# FPGA_BANKS.net
KiCad netlist of a schematic drawn in Altium Designer
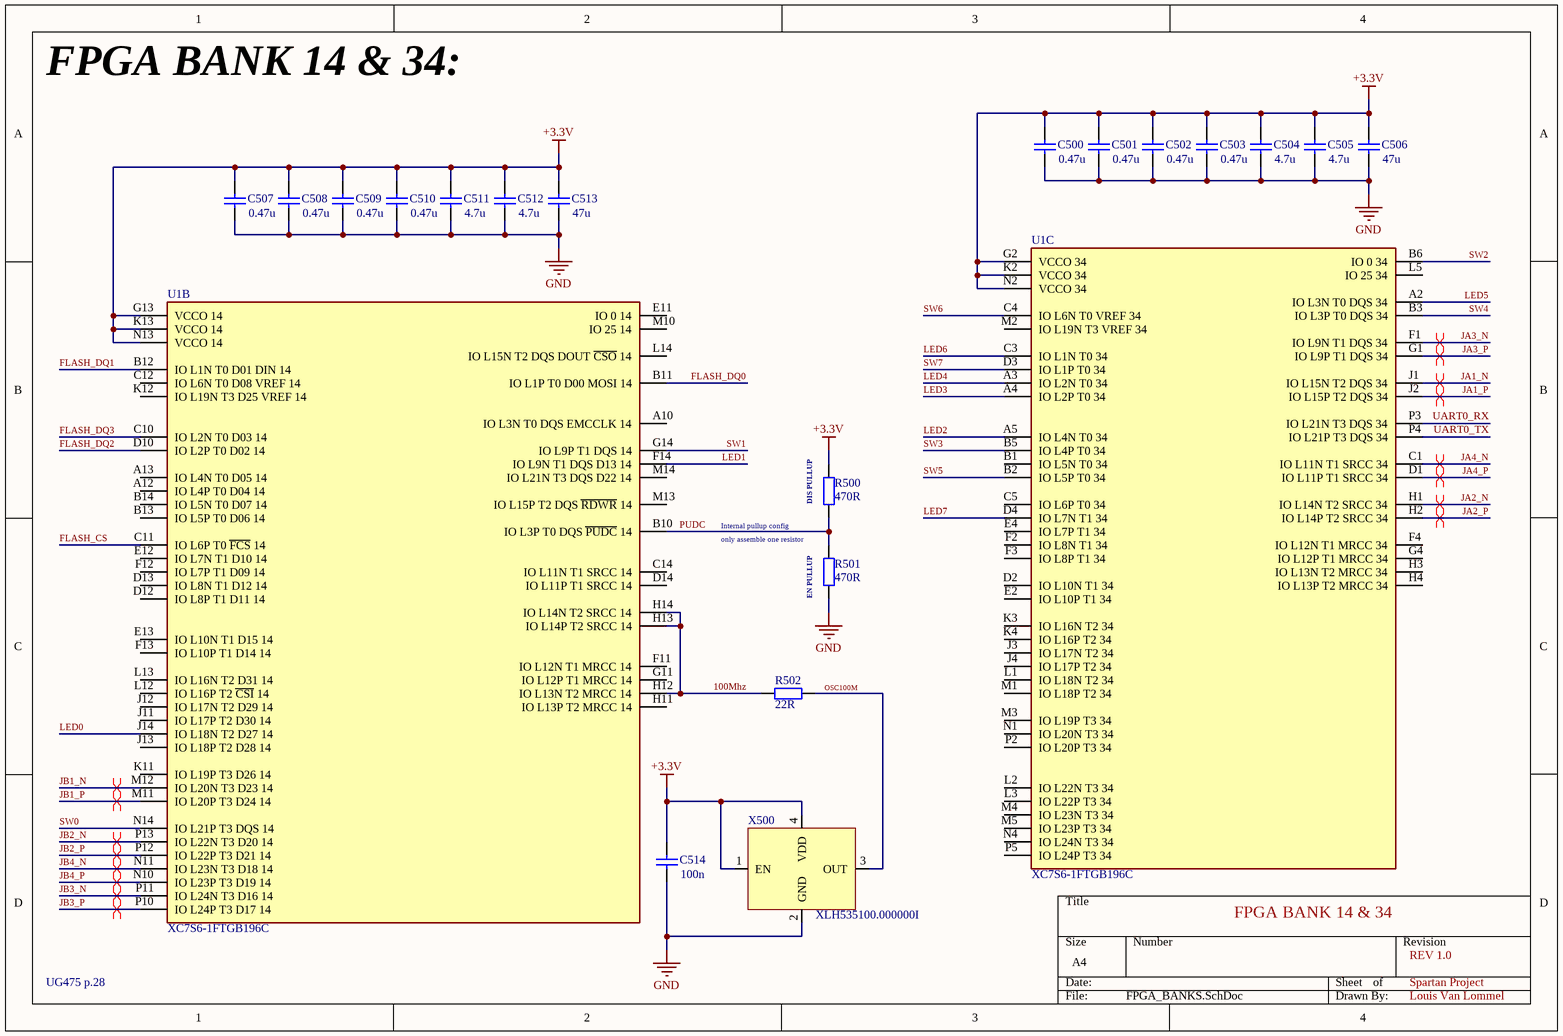
[diagram p0: FPGA_BANKS.SchDoc]

(export (version "E")
  (design (tool "Eeschema 10.0.6"))
  (components
    (comp (ref "C500")
      (value "0.47u")
      (footprint "CAP_0402")
      (description "Capacitor")
      (fields (field (name "Comment") "0.47uF") (field (name "PUBLISHER") "Altium Limited"))
      (libsource (lib "Miscellaneous Devices") (part "Cap"))
    )
    (comp (ref "C501")
      (value "0.47u")
      (footprint "CAP_0402")
      (description "Capacitor")
      (fields (field (name "Comment") "0.47uF") (field (name "PUBLISHER") "Altium Limited"))
      (libsource (lib "Miscellaneous Devices") (part "Cap"))
    )
    (comp (ref "C502")
      (value "0.47u")
      (footprint "CAP_0402")
      (description "Capacitor")
      (fields (field (name "Comment") "0.47uF") (field (name "PUBLISHER") "Altium Limited"))
      (libsource (lib "Miscellaneous Devices") (part "Cap"))
    )
    (comp (ref "C503")
      (value "0.47u")
      (footprint "CAP_0402")
      (description "Capacitor")
      (fields (field (name "Comment") "0.47uF") (field (name "PUBLISHER") "Altium Limited"))
      (libsource (lib "Miscellaneous Devices") (part "Cap"))
    )
    (comp (ref "C504")
      (value "4.7u")
      (footprint "CAP_0402")
      (description "Capacitor")
      (fields (field (name "PUBLISHER") "Altium Limited"))
      (libsource (lib "Miscellaneous Devices") (part "Cap"))
    )
    (comp (ref "C505")
      (value "4.7u")
      (footprint "CAP_0402")
      (description "Capacitor")
      (fields (field (name "PUBLISHER") "Altium Limited"))
      (libsource (lib "Miscellaneous Devices") (part "Cap"))
    )
    (comp (ref "C506")
      (value "47u")
      (footprint "CAP_0603")
      (description "Capacitor")
      (fields (field (name "Comment") "47uF") (field (name "PUBLISHER") "Altium Limited"))
      (libsource (lib "Miscellaneous Devices") (part "Cap"))
    )
    (comp (ref "C507")
      (value "0.47u")
      (footprint "CAP_0402")
      (description "Capacitor")
      (fields (field (name "Comment") "0.47uF") (field (name "PUBLISHER") "Altium Limited"))
      (libsource (lib "Miscellaneous Devices") (part "Cap"))
    )
    (comp (ref "C508")
      (value "0.47u")
      (footprint "CAP_0402")
      (description "Capacitor")
      (fields (field (name "Comment") "0.47uF") (field (name "PUBLISHER") "Altium Limited"))
      (libsource (lib "Miscellaneous Devices") (part "Cap"))
    )
    (comp (ref "C509")
      (value "0.47u")
      (footprint "CAP_0402")
      (description "Capacitor")
      (fields (field (name "Comment") "0.47uF") (field (name "PUBLISHER") "Altium Limited"))
      (libsource (lib "Miscellaneous Devices") (part "Cap"))
    )
    (comp (ref "C510")
      (value "0.47u")
      (footprint "CAP_0402")
      (description "Capacitor")
      (fields (field (name "Comment") "0.47uF") (field (name "PUBLISHER") "Altium Limited"))
      (libsource (lib "Miscellaneous Devices") (part "Cap"))
    )
    (comp (ref "C511")
      (value "4.7u")
      (footprint "CAP_0402")
      (description "Capacitor")
      (fields (field (name "PUBLISHER") "Altium Limited"))
      (libsource (lib "Miscellaneous Devices") (part "Cap"))
    )
    (comp (ref "C512")
      (value "4.7u")
      (footprint "CAP_0402")
      (description "Capacitor")
      (fields (field (name "PUBLISHER") "Altium Limited"))
      (libsource (lib "Miscellaneous Devices") (part "Cap"))
    )
    (comp (ref "C513")
      (value "47u")
      (footprint "CAP_0603")
      (description "Capacitor")
      (fields (field (name "Comment") "47uF") (field (name "PUBLISHER") "Altium Limited"))
      (libsource (lib "Miscellaneous Devices") (part "Cap"))
    )
    (comp (ref "C514")
      (value "100n")
      (footprint "CAP_0603")
      (description "Capacitor")
      (fields (field (name "PUBLISHER") "Altium Limited"))
      (libsource (lib "Miscellaneous Devices") (part "Cap"))
    )
    (comp (ref "R500")
      (value "470R")
      (footprint "RES_0603")
      (description "Resistor")
      (fields (field (name "Comment") "470") (field (name "PUBLISHER") "Altium Limited"))
      (libsource (lib "Miscellaneous Devices") (part "Res2"))
    )
    (comp (ref "R501")
      (value "470R")
      (footprint "RES_0603")
      (description "Resistor Enable pullup BANK FPGA")
      (fields (field (name "Comment") "470 DNP") (field (name "PUBLISHER") "Altium Limited"))
      (libsource (lib "Miscellaneous Devices") (part "Res2"))
    )
    (comp (ref "R502")
      (value "22R")
      (footprint "RES_0603")
      (description "Resistor")
      (fields (field (name "Comment") "22") (field (name "PUBLISHER") "Altium Limited"))
      (libsource (lib "") (part "Res2_1"))
    )
    (comp (ref "U1")
      (value "XC7S6-1FTGB196C")
      (footprint "FP-XC7S6-1FTGB196C-MFG")
      (fields
        (field (name "MANUFACTURER") "Xilinx")
        (field (name "OCTOPART") "https://octopart.com/xc7s6-1ftgb196c-xilinx-81890684")
      )
      (libsource (lib "Altium Content Vault") (part "4382e9425a5ef0cb43184b1739abe55"))
    )
    (comp (ref "X500")
      (value "XLH535100.000000I")
      (footprint "5X3.2MM CRYSTAL")
      (description "12Mhz oscillator")
      (libsource (lib "Schematic_Symbols") (part "Oscillator"))
    )
  )
  (nets
    (net (code "1") (name "+3.3V") (class "Default")
      (node (ref "C500") (pin "2") (pinfunction "2_2") (pintype "passive"))
      (node (ref "C501") (pin "2") (pinfunction "2_2") (pintype "passive"))
      (node (ref "C502") (pin "2") (pinfunction "2_2") (pintype "passive"))
      (node (ref "C503") (pin "2") (pinfunction "2_2") (pintype "passive"))
      (node (ref "C504") (pin "2") (pinfunction "2_2") (pintype "passive"))
      (node (ref "C505") (pin "2") (pinfunction "2_2") (pintype "passive"))
      (node (ref "C506") (pin "2") (pinfunction "2_2") (pintype "passive"))
      (node (ref "C507") (pin "2") (pinfunction "2_2") (pintype "passive"))
      (node (ref "C508") (pin "2") (pinfunction "2_2") (pintype "passive"))
      (node (ref "C509") (pin "2") (pinfunction "2_2") (pintype "passive"))
      (node (ref "C510") (pin "2") (pinfunction "2_2") (pintype "passive"))
      (node (ref "C511") (pin "2") (pinfunction "2_2") (pintype "passive"))
      (node (ref "C512") (pin "2") (pinfunction "2_2") (pintype "passive"))
      (node (ref "C513") (pin "2") (pinfunction "2_2") (pintype "passive"))
      (node (ref "C514") (pin "2") (pinfunction "2_2") (pintype "passive"))
      (node (ref "R500") (pin "2") (pinfunction "2_2") (pintype "passive"))
      (node (ref "U1") (pin "G13") (pinfunction "VCCO_14_G13") (pintype "passive"))
      (node (ref "U1") (pin "G2") (pinfunction "VCCO_34_G2") (pintype "passive"))
      (node (ref "U1") (pin "K13") (pinfunction "VCCO_14_K13") (pintype "passive"))
      (node (ref "U1") (pin "K2") (pinfunction "VCCO_34_K2") (pintype "passive"))
      (node (ref "U1") (pin "N13") (pinfunction "VCCO_14_N13") (pintype "passive"))
      (node (ref "U1") (pin "N2") (pinfunction "VCCO_34_N2") (pintype "passive"))
      (node (ref "X500") (pin "1") (pinfunction "EN_1") (pintype "passive"))
      (node (ref "X500") (pin "4") (pinfunction "VDD_4") (pintype "passive"))
    )
    (net (code "2") (name "/100Mhz") (class "Default")
      (node (ref "R502") (pin "2") (pinfunction "2_2") (pintype "passive"))
      (node (ref "U1") (pin "H12") (pinfunction "IO_L13N_T2_MRCC_14_H12") (pintype "passive"))
      (node (ref "U1") (pin "H13") (pinfunction "IO_L14P_T2_SRCC_14_H13") (pintype "passive"))
      (node (ref "U1") (pin "H14") (pinfunction "IO_L14N_T2_SRCC_14_H14") (pintype "passive"))
    )
    (net (code "3") (name "/FLASH_CS") (class "Default")
      (node (ref "U1") (pin "C11") (pinfunction "IO_L6P_T0_~{FCS}_14_C11") (pintype "passive"))
    )
    (net (code "4") (name "/FLASH_DQ0") (class "Default")
      (node (ref "U1") (pin "B11") (pinfunction "IO_L1P_T0_D00_MOSI_14_B11") (pintype "passive"))
    )
    (net (code "5") (name "/FLASH_DQ1") (class "Default")
      (node (ref "U1") (pin "B12") (pinfunction "IO_L1N_T0_D01_DIN_14_B12") (pintype "passive"))
    )
    (net (code "6") (name "/FLASH_DQ2") (class "Default")
      (node (ref "U1") (pin "D10") (pinfunction "IO_L2P_T0_D02_14_D10") (pintype "passive"))
    )
    (net (code "7") (name "/FLASH_DQ3") (class "Default")
      (node (ref "U1") (pin "C10") (pinfunction "IO_L2N_T0_D03_14_C10") (pintype "passive"))
    )
    (net (code "8") (name "/JA1_N") (class "Default")
      (node (ref "U1") (pin "J1") (pinfunction "IO_L15N_T2_DQS_34_J1") (pintype "passive"))
    )
    (net (code "9") (name "/JA1_P") (class "Default")
      (node (ref "U1") (pin "J2") (pinfunction "IO_L15P_T2_DQS_34_J2") (pintype "passive"))
    )
    (net (code "10") (name "/JA2_N") (class "Default")
      (node (ref "U1") (pin "H1") (pinfunction "IO_L14N_T2_SRCC_34_H1") (pintype "passive"))
    )
    (net (code "11") (name "/JA2_P") (class "Default")
      (node (ref "U1") (pin "H2") (pinfunction "IO_L14P_T2_SRCC_34_H2") (pintype "passive"))
    )
    (net (code "12") (name "/JA3_N") (class "Default")
      (node (ref "U1") (pin "F1") (pinfunction "IO_L9N_T1_DQS_34_F1") (pintype "passive"))
    )
    (net (code "13") (name "/JA3_P") (class "Default")
      (node (ref "U1") (pin "G1") (pinfunction "IO_L9P_T1_DQS_34_G1") (pintype "passive"))
    )
    (net (code "14") (name "/JA4_N") (class "Default")
      (node (ref "U1") (pin "C1") (pinfunction "IO_L11N_T1_SRCC_34_C1") (pintype "passive"))
    )
    (net (code "15") (name "/JA4_P") (class "Default")
      (node (ref "U1") (pin "D1") (pinfunction "IO_L11P_T1_SRCC_34_D1") (pintype "passive"))
    )
    (net (code "16") (name "/JB1_N") (class "Default")
      (node (ref "U1") (pin "M12") (pinfunction "IO_L20N_T3_D23_14_M12") (pintype "passive"))
    )
    (net (code "17") (name "/JB1_P") (class "Default")
      (node (ref "U1") (pin "M11") (pinfunction "IO_L20P_T3_D24_14_M11") (pintype "passive"))
    )
    (net (code "18") (name "/JB2_N") (class "Default")
      (node (ref "U1") (pin "P13") (pinfunction "IO_L22N_T3_D20_14_P13") (pintype "passive"))
    )
    (net (code "19") (name "/JB2_P") (class "Default")
      (node (ref "U1") (pin "P12") (pinfunction "IO_L22P_T3_D21_14_P12") (pintype "passive"))
    )
    (net (code "20") (name "/JB3_N") (class "Default")
      (node (ref "U1") (pin "P11") (pinfunction "IO_L24N_T3_D16_14_P11") (pintype "passive"))
    )
    (net (code "21") (name "/JB3_P") (class "Default")
      (node (ref "U1") (pin "P10") (pinfunction "IO_L24P_T3_D17_14_P10") (pintype "passive"))
    )
    (net (code "22") (name "/JB4_N") (class "Default")
      (node (ref "U1") (pin "N11") (pinfunction "IO_L23N_T3_D18_14_N11") (pintype "passive"))
    )
    (net (code "23") (name "/JB4_P") (class "Default")
      (node (ref "U1") (pin "N10") (pinfunction "IO_L23P_T3_D19_14_N10") (pintype "passive"))
    )
    (net (code "24") (name "/LED0") (class "Default")
      (node (ref "U1") (pin "J14") (pinfunction "IO_L18N_T2_D27_14_J14") (pintype "passive"))
    )
    (net (code "25") (name "/LED1") (class "Default")
      (node (ref "U1") (pin "F14") (pinfunction "IO_L9N_T1_DQS_D13_14_F14") (pintype "passive"))
    )
    (net (code "26") (name "/LED2") (class "Default")
      (node (ref "U1") (pin "A5") (pinfunction "IO_L4N_T0_34_A5") (pintype "passive"))
    )
    (net (code "27") (name "/LED3") (class "Default")
      (node (ref "U1") (pin "A4") (pinfunction "IO_L2P_T0_34_A4") (pintype "passive"))
    )
    (net (code "28") (name "/LED4") (class "Default")
      (node (ref "U1") (pin "A3") (pinfunction "IO_L2N_T0_34_A3") (pintype "passive"))
    )
    (net (code "29") (name "/LED5") (class "Default")
      (node (ref "U1") (pin "A2") (pinfunction "IO_L3N_T0_DQS_34_A2") (pintype "passive"))
    )
    (net (code "30") (name "/LED6") (class "Default")
      (node (ref "U1") (pin "C3") (pinfunction "IO_L1N_T0_34_C3") (pintype "passive"))
    )
    (net (code "31") (name "/LED7") (class "Default")
      (node (ref "U1") (pin "D4") (pinfunction "IO_L7N_T1_34_D4") (pintype "passive"))
    )
    (net (code "32") (name "/OSC100M") (class "Default")
      (node (ref "R502") (pin "1") (pinfunction "1_1") (pintype "passive"))
      (node (ref "X500") (pin "3") (pinfunction "OUT_3") (pintype "passive"))
    )
    (net (code "33") (name "/PUDC") (class "Default")
      (node (ref "R500") (pin "1") (pinfunction "1_1") (pintype "passive"))
      (node (ref "R501") (pin "2") (pinfunction "2_2") (pintype "passive"))
      (node (ref "U1") (pin "B10") (pinfunction "IO_L3P_T0_DQS_~{PUDC}_14_B10") (pintype "passive"))
    )
    (net (code "34") (name "/SW0") (class "Default")
      (node (ref "U1") (pin "N14") (pinfunction "IO_L21P_T3_DQS_14_N14") (pintype "passive"))
    )
    (net (code "35") (name "/SW1") (class "Default")
      (node (ref "U1") (pin "G14") (pinfunction "IO_L9P_T1_DQS_14_G14") (pintype "passive"))
    )
    (net (code "36") (name "/SW2") (class "Default")
      (node (ref "U1") (pin "B6") (pinfunction "IO_0_34_B6") (pintype "passive"))
    )
    (net (code "37") (name "/SW3") (class "Default")
      (node (ref "U1") (pin "B5") (pinfunction "IO_L4P_T0_34_B5") (pintype "passive"))
    )
    (net (code "38") (name "/SW4") (class "Default")
      (node (ref "U1") (pin "B3") (pinfunction "IO_L3P_T0_DQS_34_B3") (pintype "passive"))
    )
    (net (code "39") (name "/SW5") (class "Default")
      (node (ref "U1") (pin "B2") (pinfunction "IO_L5P_T0_34_B2") (pintype "passive"))
    )
    (net (code "40") (name "/SW6") (class "Default")
      (node (ref "U1") (pin "C4") (pinfunction "IO_L6N_T0_VREF_34_C4") (pintype "passive"))
    )
    (net (code "41") (name "/SW7") (class "Default")
      (node (ref "U1") (pin "D3") (pinfunction "IO_L1P_T0_34_D3") (pintype "passive"))
    )
    (net (code "42") (name "/UART0_RX") (class "Default")
      (node (ref "U1") (pin "P3") (pinfunction "IO_L21N_T3_DQS_34_P3") (pintype "passive"))
    )
    (net (code "43") (name "/UART0_TX") (class "Default")
      (node (ref "U1") (pin "P4") (pinfunction "IO_L21P_T3_DQS_34_P4") (pintype "passive"))
    )
    (net (code "44") (name "GND") (class "Default")
      (node (ref "C500") (pin "1") (pinfunction "1_1") (pintype "passive"))
      (node (ref "C501") (pin "1") (pinfunction "1_1") (pintype "passive"))
      (node (ref "C502") (pin "1") (pinfunction "1_1") (pintype "passive"))
      (node (ref "C503") (pin "1") (pinfunction "1_1") (pintype "passive"))
      (node (ref "C504") (pin "1") (pinfunction "1_1") (pintype "passive"))
      (node (ref "C505") (pin "1") (pinfunction "1_1") (pintype "passive"))
      (node (ref "C506") (pin "1") (pinfunction "1_1") (pintype "passive"))
      (node (ref "C507") (pin "1") (pinfunction "1_1") (pintype "passive"))
      (node (ref "C508") (pin "1") (pinfunction "1_1") (pintype "passive"))
      (node (ref "C509") (pin "1") (pinfunction "1_1") (pintype "passive"))
      (node (ref "C510") (pin "1") (pinfunction "1_1") (pintype "passive"))
      (node (ref "C511") (pin "1") (pinfunction "1_1") (pintype "passive"))
      (node (ref "C512") (pin "1") (pinfunction "1_1") (pintype "passive"))
      (node (ref "C513") (pin "1") (pinfunction "1_1") (pintype "passive"))
      (node (ref "C514") (pin "1") (pinfunction "1_1") (pintype "passive"))
      (node (ref "R501") (pin "1") (pinfunction "1_1") (pintype "passive"))
      (node (ref "X500") (pin "2") (pinfunction "GND_2") (pintype "passive"))
    )
    (net (code "45") (name "unconnected-(U1B-IO_0_14-PadE11)") (class "Default")
      (node (ref "U1") (pin "E11") (pinfunction "IO_0_14_E11") (pintype "passive"))
    )
    (net (code "46") (name "unconnected-(U1B-IO_25_14-PadM10)") (class "Default")
      (node (ref "U1") (pin "M10") (pinfunction "IO_25_14_M10") (pintype "passive"))
    )
    (net (code "47") (name "unconnected-(U1B-IO_L3N_T0_DQS_EMCCLK_14-PadA10)") (class "Default")
      (node (ref "U1") (pin "A10") (pinfunction "IO_L3N_T0_DQS_EMCCLK_14_A10") (pintype "passive"))
    )
    (net (code "48") (name "unconnected-(U1B-IO_L4N_T0_D05_14-PadA13)") (class "Default")
      (node (ref "U1") (pin "A13") (pinfunction "IO_L4N_T0_D05_14_A13") (pintype "passive"))
    )
    (net (code "49") (name "unconnected-(U1B-IO_L4P_T0_D04_14-PadA12)") (class "Default")
      (node (ref "U1") (pin "A12") (pinfunction "IO_L4P_T0_D04_14_A12") (pintype "passive"))
    )
    (net (code "50") (name "unconnected-(U1B-IO_L5N_T0_D07_14-PadB14)") (class "Default")
      (node (ref "U1") (pin "B14") (pinfunction "IO_L5N_T0_D07_14_B14") (pintype "passive"))
    )
    (net (code "51") (name "unconnected-(U1B-IO_L5P_T0_D06_14-PadB13)") (class "Default")
      (node (ref "U1") (pin "B13") (pinfunction "IO_L5P_T0_D06_14_B13") (pintype "passive"))
    )
    (net (code "52") (name "unconnected-(U1B-IO_L6N_T0_D08_VREF_14-PadC12)") (class "Default")
      (node (ref "U1") (pin "C12") (pinfunction "IO_L6N_T0_D08_VREF_14_C12") (pintype "passive"))
    )
    (net (code "53") (name "unconnected-(U1B-IO_L7N_T1_D10_14-PadE12)") (class "Default")
      (node (ref "U1") (pin "E12") (pinfunction "IO_L7N_T1_D10_14_E12") (pintype "passive"))
    )
    (net (code "54") (name "unconnected-(U1B-IO_L7P_T1_D09_14-PadF12)") (class "Default")
      (node (ref "U1") (pin "F12") (pinfunction "IO_L7P_T1_D09_14_F12") (pintype "passive"))
    )
    (net (code "55") (name "unconnected-(U1B-IO_L8N_T1_D12_14-PadD13)") (class "Default")
      (node (ref "U1") (pin "D13") (pinfunction "IO_L8N_T1_D12_14_D13") (pintype "passive"))
    )
    (net (code "56") (name "unconnected-(U1B-IO_L8P_T1_D11_14-PadD12)") (class "Default")
      (node (ref "U1") (pin "D12") (pinfunction "IO_L8P_T1_D11_14_D12") (pintype "passive"))
    )
    (net (code "57") (name "unconnected-(U1B-IO_L10N_T1_D15_14-PadE13)") (class "Default")
      (node (ref "U1") (pin "E13") (pinfunction "IO_L10N_T1_D15_14_E13") (pintype "passive"))
    )
    (net (code "58") (name "unconnected-(U1B-IO_L10P_T1_D14_14-PadF13)") (class "Default")
      (node (ref "U1") (pin "F13") (pinfunction "IO_L10P_T1_D14_14_F13") (pintype "passive"))
    )
    (net (code "59") (name "unconnected-(U1B-IO_L11N_T1_SRCC_14-PadC14)") (class "Default")
      (node (ref "U1") (pin "C14") (pinfunction "IO_L11N_T1_SRCC_14_C14") (pintype "passive"))
    )
    (net (code "60") (name "unconnected-(U1B-IO_L11P_T1_SRCC_14-PadD14)") (class "Default")
      (node (ref "U1") (pin "D14") (pinfunction "IO_L11P_T1_SRCC_14_D14") (pintype "passive"))
    )
    (net (code "61") (name "unconnected-(U1B-IO_L12N_T1_MRCC_14-PadF11)") (class "Default")
      (node (ref "U1") (pin "F11") (pinfunction "IO_L12N_T1_MRCC_14_F11") (pintype "passive"))
    )
    (net (code "62") (name "unconnected-(U1B-IO_L12P_T1_MRCC_14-PadG11)") (class "Default")
      (node (ref "U1") (pin "G11") (pinfunction "IO_L12P_T1_MRCC_14_G11") (pintype "passive"))
    )
    (net (code "63") (name "unconnected-(U1B-IO_L13P_T2_MRCC_14-PadH11)") (class "Default")
      (node (ref "U1") (pin "H11") (pinfunction "IO_L13P_T2_MRCC_14_H11") (pintype "passive"))
    )
    (net (code "64") (name "unconnected-(U1B-IO_L15N_T2_DQS_DOUT_~{CSO}_14-PadL14)") (class "Default")
      (node (ref "U1") (pin "L14") (pinfunction "IO_L15N_T2_DQS_DOUT_~{CSO}_14_L14") (pintype "passive"))
    )
    (net (code "65") (name "unconnected-(U1B-IO_L15P_T2_DQS_~{RDWR}_14-PadM13)") (class "Default")
      (node (ref "U1") (pin "M13") (pinfunction "IO_L15P_T2_DQS_~{RDWR}_14_M13") (pintype "passive"))
    )
    (net (code "66") (name "unconnected-(U1B-IO_L16N_T2_D31_14-PadL13)") (class "Default")
      (node (ref "U1") (pin "L13") (pinfunction "IO_L16N_T2_D31_14_L13") (pintype "passive"))
    )
    (net (code "67") (name "unconnected-(U1B-IO_L16P_T2_~{CSI}_14-PadL12)") (class "Default")
      (node (ref "U1") (pin "L12") (pinfunction "IO_L16P_T2_~{CSI}_14_L12") (pintype "passive"))
    )
    (net (code "68") (name "unconnected-(U1B-IO_L17N_T2_D29_14-PadJ12)") (class "Default")
      (node (ref "U1") (pin "J12") (pinfunction "IO_L17N_T2_D29_14_J12") (pintype "passive"))
    )
    (net (code "69") (name "unconnected-(U1B-IO_L17P_T2_D30_14-PadJ11)") (class "Default")
      (node (ref "U1") (pin "J11") (pinfunction "IO_L17P_T2_D30_14_J11") (pintype "passive"))
    )
    (net (code "70") (name "unconnected-(U1B-IO_L18P_T2_D28_14-PadJ13)") (class "Default")
      (node (ref "U1") (pin "J13") (pinfunction "IO_L18P_T2_D28_14_J13") (pintype "passive"))
    )
    (net (code "71") (name "unconnected-(U1B-IO_L19N_T3_D25_VREF_14-PadK12)") (class "Default")
      (node (ref "U1") (pin "K12") (pinfunction "IO_L19N_T3_D25_VREF_14_K12") (pintype "passive"))
    )
    (net (code "72") (name "unconnected-(U1B-IO_L19P_T3_D26_14-PadK11)") (class "Default")
      (node (ref "U1") (pin "K11") (pinfunction "IO_L19P_T3_D26_14_K11") (pintype "passive"))
    )
    (net (code "73") (name "unconnected-(U1B-IO_L21N_T3_DQS_D22_14-PadM14)") (class "Default")
      (node (ref "U1") (pin "M14") (pinfunction "IO_L21N_T3_DQS_D22_14_M14") (pintype "passive"))
    )
    (net (code "74") (name "unconnected-(U1C-IO_25_34-PadL5)") (class "Default")
      (node (ref "U1") (pin "L5") (pinfunction "IO_25_34_L5") (pintype "passive"))
    )
    (net (code "75") (name "unconnected-(U1C-IO_L5N_T0_34-PadB1)") (class "Default")
      (node (ref "U1") (pin "B1") (pinfunction "IO_L5N_T0_34_B1") (pintype "passive"))
    )
    (net (code "76") (name "unconnected-(U1C-IO_L6P_T0_34-PadC5)") (class "Default")
      (node (ref "U1") (pin "C5") (pinfunction "IO_L6P_T0_34_C5") (pintype "passive"))
    )
    (net (code "77") (name "unconnected-(U1C-IO_L7P_T1_34-PadE4)") (class "Default")
      (node (ref "U1") (pin "E4") (pinfunction "IO_L7P_T1_34_E4") (pintype "passive"))
    )
    (net (code "78") (name "unconnected-(U1C-IO_L8N_T1_34-PadF2)") (class "Default")
      (node (ref "U1") (pin "F2") (pinfunction "IO_L8N_T1_34_F2") (pintype "passive"))
    )
    (net (code "79") (name "unconnected-(U1C-IO_L8P_T1_34-PadF3)") (class "Default")
      (node (ref "U1") (pin "F3") (pinfunction "IO_L8P_T1_34_F3") (pintype "passive"))
    )
    (net (code "80") (name "unconnected-(U1C-IO_L10N_T1_34-PadD2)") (class "Default")
      (node (ref "U1") (pin "D2") (pinfunction "IO_L10N_T1_34_D2") (pintype "passive"))
    )
    (net (code "81") (name "unconnected-(U1C-IO_L10P_T1_34-PadE2)") (class "Default")
      (node (ref "U1") (pin "E2") (pinfunction "IO_L10P_T1_34_E2") (pintype "passive"))
    )
    (net (code "82") (name "unconnected-(U1C-IO_L12N_T1_MRCC_34-PadF4)") (class "Default")
      (node (ref "U1") (pin "F4") (pinfunction "IO_L12N_T1_MRCC_34_F4") (pintype "passive"))
    )
    (net (code "83") (name "unconnected-(U1C-IO_L12P_T1_MRCC_34-PadG4)") (class "Default")
      (node (ref "U1") (pin "G4") (pinfunction "IO_L12P_T1_MRCC_34_G4") (pintype "passive"))
    )
    (net (code "84") (name "unconnected-(U1C-IO_L13N_T2_MRCC_34-PadH3)") (class "Default")
      (node (ref "U1") (pin "H3") (pinfunction "IO_L13N_T2_MRCC_34_H3") (pintype "passive"))
    )
    (net (code "85") (name "unconnected-(U1C-IO_L13P_T2_MRCC_34-PadH4)") (class "Default")
      (node (ref "U1") (pin "H4") (pinfunction "IO_L13P_T2_MRCC_34_H4") (pintype "passive"))
    )
    (net (code "86") (name "unconnected-(U1C-IO_L16N_T2_34-PadK3)") (class "Default")
      (node (ref "U1") (pin "K3") (pinfunction "IO_L16N_T2_34_K3") (pintype "passive"))
    )
    (net (code "87") (name "unconnected-(U1C-IO_L16P_T2_34-PadK4)") (class "Default")
      (node (ref "U1") (pin "K4") (pinfunction "IO_L16P_T2_34_K4") (pintype "passive"))
    )
    (net (code "88") (name "unconnected-(U1C-IO_L17N_T2_34-PadJ3)") (class "Default")
      (node (ref "U1") (pin "J3") (pinfunction "IO_L17N_T2_34_J3") (pintype "passive"))
    )
    (net (code "89") (name "unconnected-(U1C-IO_L17P_T2_34-PadJ4)") (class "Default")
      (node (ref "U1") (pin "J4") (pinfunction "IO_L17P_T2_34_J4") (pintype "passive"))
    )
    (net (code "90") (name "unconnected-(U1C-IO_L18N_T2_34-PadL1)") (class "Default")
      (node (ref "U1") (pin "L1") (pinfunction "IO_L18N_T2_34_L1") (pintype "passive"))
    )
    (net (code "91") (name "unconnected-(U1C-IO_L18P_T2_34-PadM1)") (class "Default")
      (node (ref "U1") (pin "M1") (pinfunction "IO_L18P_T2_34_M1") (pintype "passive"))
    )
    (net (code "92") (name "unconnected-(U1C-IO_L19N_T3_VREF_34-PadM2)") (class "Default")
      (node (ref "U1") (pin "M2") (pinfunction "IO_L19N_T3_VREF_34_M2") (pintype "passive"))
    )
    (net (code "93") (name "unconnected-(U1C-IO_L19P_T3_34-PadM3)") (class "Default")
      (node (ref "U1") (pin "M3") (pinfunction "IO_L19P_T3_34_M3") (pintype "passive"))
    )
    (net (code "94") (name "unconnected-(U1C-IO_L20N_T3_34-PadN1)") (class "Default")
      (node (ref "U1") (pin "N1") (pinfunction "IO_L20N_T3_34_N1") (pintype "passive"))
    )
    (net (code "95") (name "unconnected-(U1C-IO_L20P_T3_34-PadP2)") (class "Default")
      (node (ref "U1") (pin "P2") (pinfunction "IO_L20P_T3_34_P2") (pintype "passive"))
    )
    (net (code "96") (name "unconnected-(U1C-IO_L22N_T3_34-PadL2)") (class "Default")
      (node (ref "U1") (pin "L2") (pinfunction "IO_L22N_T3_34_L2") (pintype "passive"))
    )
    (net (code "97") (name "unconnected-(U1C-IO_L22P_T3_34-PadL3)") (class "Default")
      (node (ref "U1") (pin "L3") (pinfunction "IO_L22P_T3_34_L3") (pintype "passive"))
    )
    (net (code "98") (name "unconnected-(U1C-IO_L23N_T3_34-PadM4)") (class "Default")
      (node (ref "U1") (pin "M4") (pinfunction "IO_L23N_T3_34_M4") (pintype "passive"))
    )
    (net (code "99") (name "unconnected-(U1C-IO_L23P_T3_34-PadM5)") (class "Default")
      (node (ref "U1") (pin "M5") (pinfunction "IO_L23P_T3_34_M5") (pintype "passive"))
    )
    (net (code "100") (name "unconnected-(U1C-IO_L24N_T3_34-PadN4)") (class "Default")
      (node (ref "U1") (pin "N4") (pinfunction "IO_L24N_T3_34_N4") (pintype "passive"))
    )
    (net (code "101") (name "unconnected-(U1C-IO_L24P_T3_34-PadP5)") (class "Default")
      (node (ref "U1") (pin "P5") (pinfunction "IO_L24P_T3_34_P5") (pintype "passive"))
    )
  )
)
